# ProPrj_pbsy3_0_2025-02-05.net
KiCad netlist of a schematic drawn in EasyEDA Pro
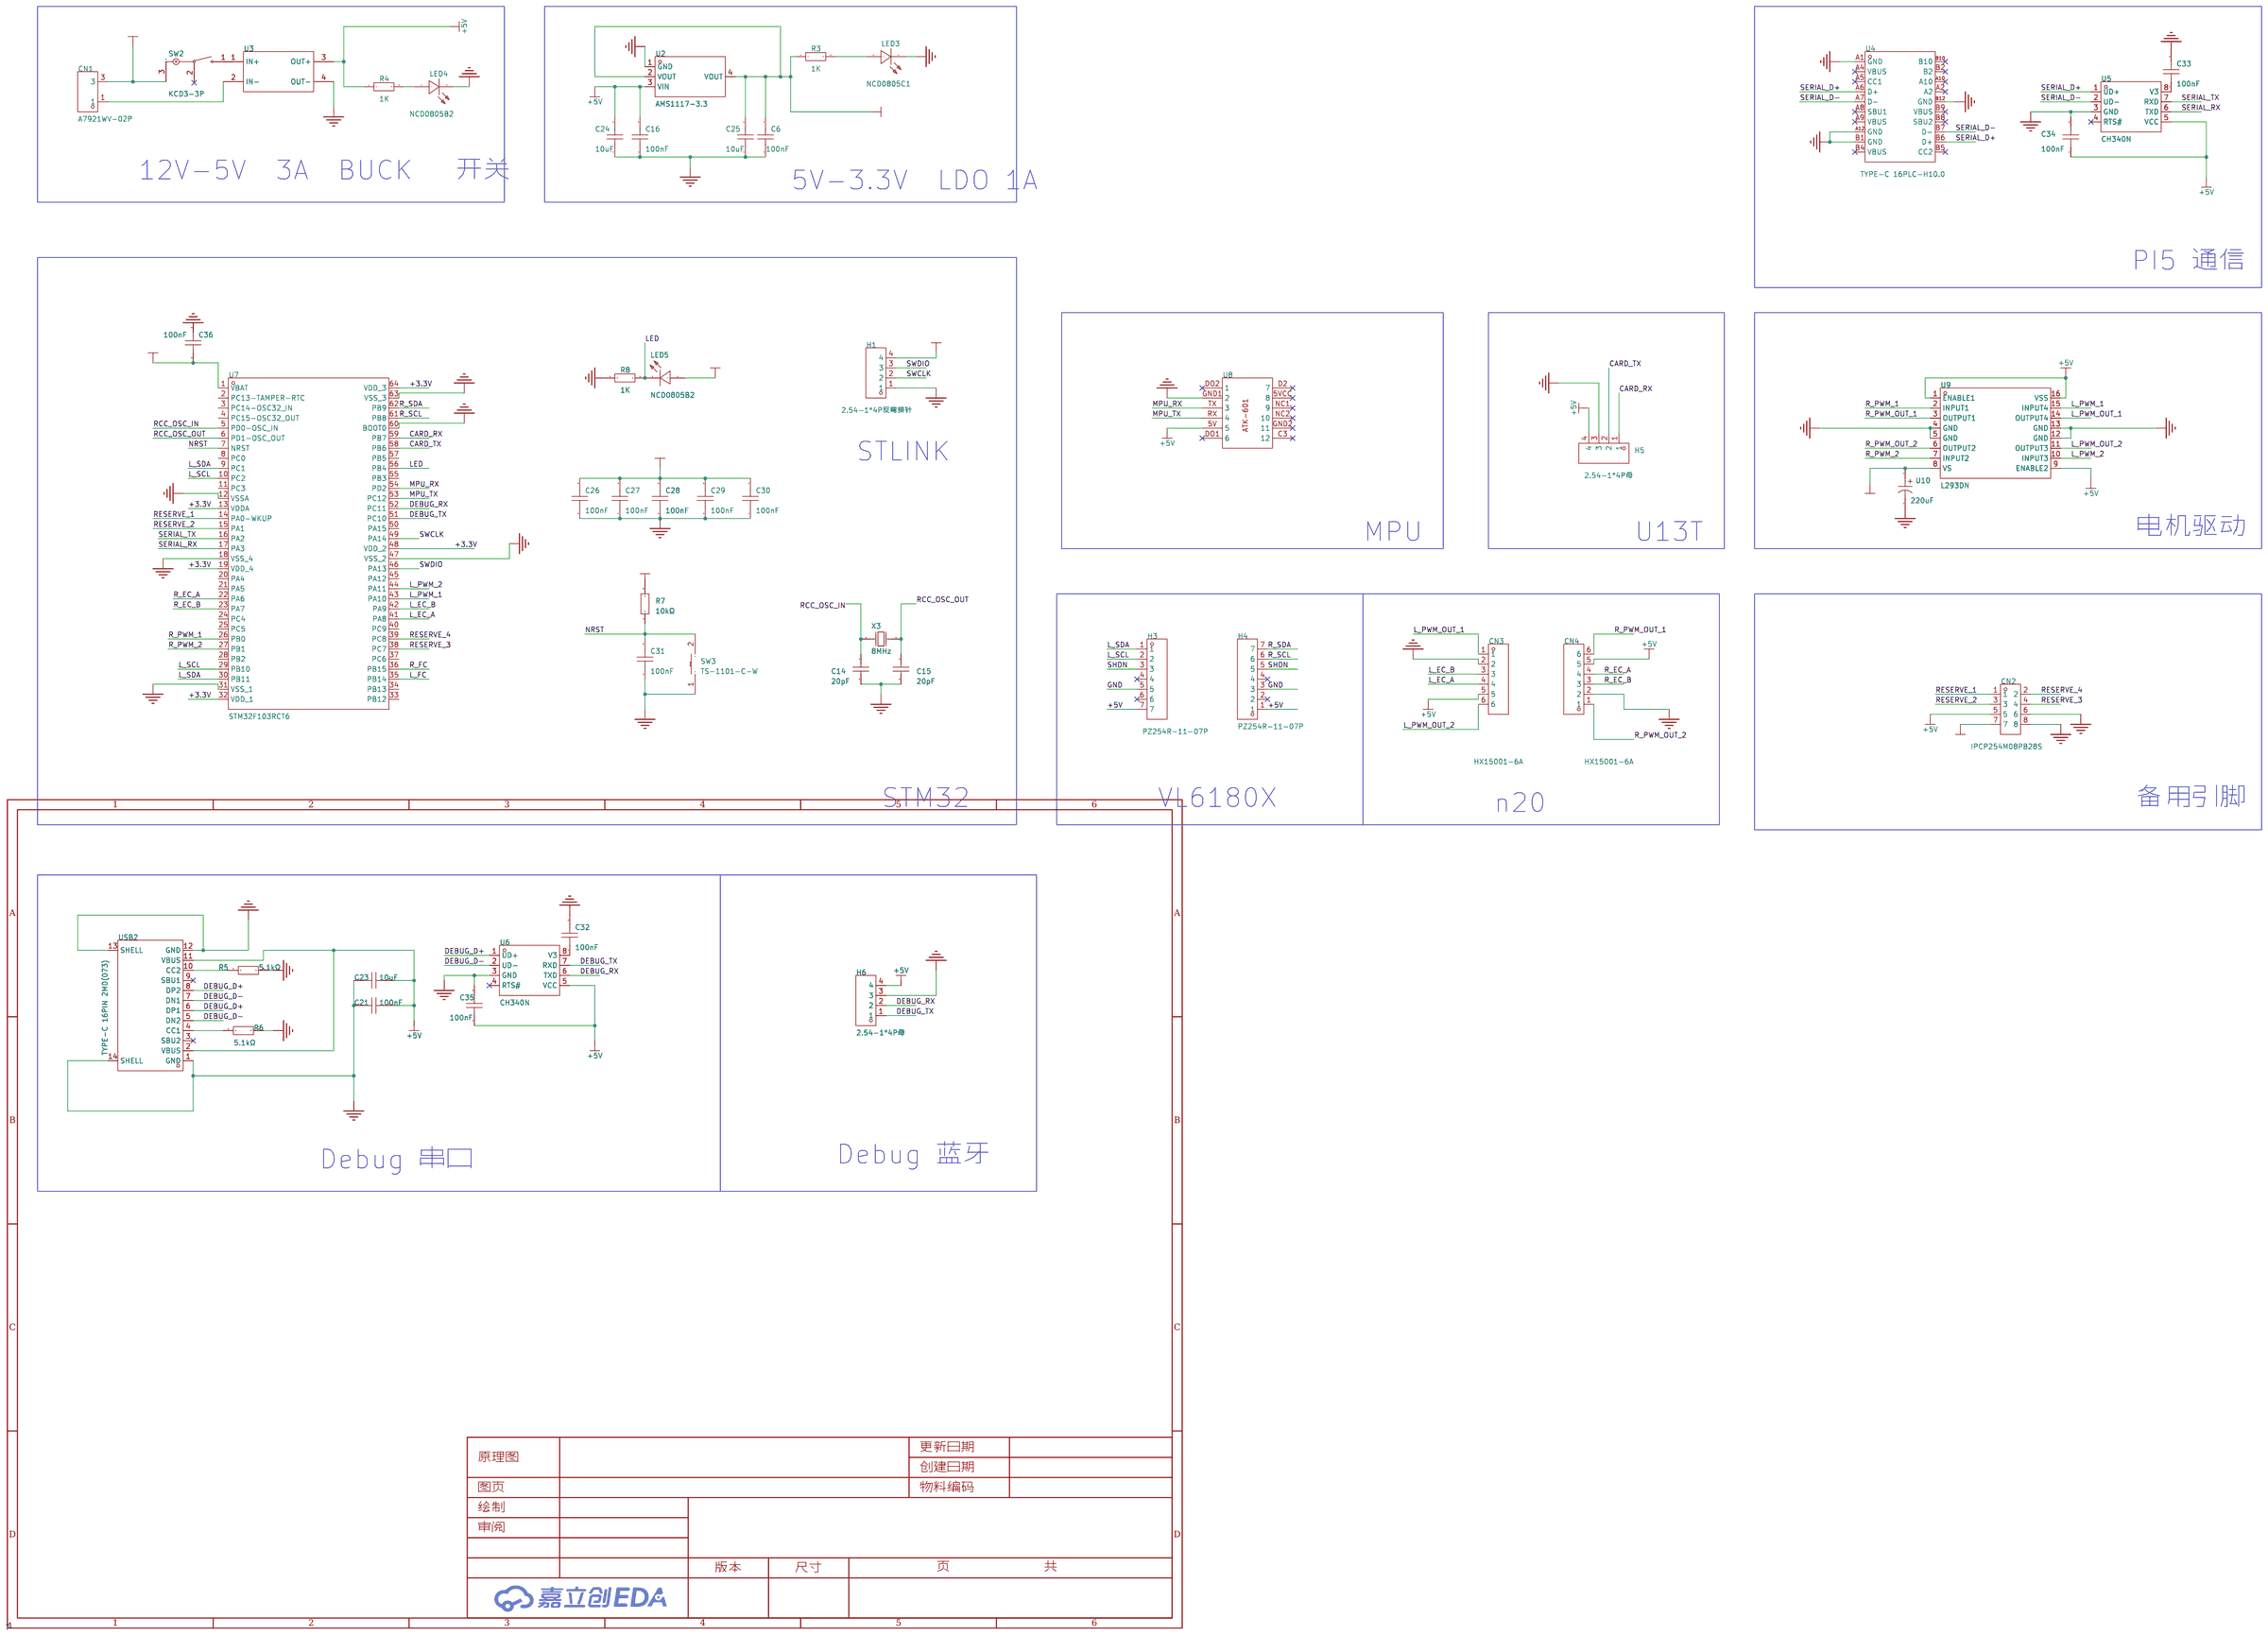
[diagram p0: schematic sheet]

(export (version "E")
  (design (tool "Eeschema 10.0.6"))
  (components
    (comp (ref "C6")
      (value "100nF")
      (footprint "easyedapro:C0603")
      (description "容值:100nF;精度:±10%;额定电压:50V;材质(温度系数):X7R;")
      (fields
        (field (name "Manufacturer Part") "CC0603KRX7R9BB104")
        (field (name "Manufacturer") "YAGEO(国巨)")
      )
      (libsource (lib "easyedapro") (part "CC0603KRX7R9BB104"))
    )
    (comp (ref "C14")
      (value "20pF")
      (footprint "easyedapro:C0805")
      (description "容值:20pF;精度:±5%;额定电压:50V;材质(温度系数):C0G;")
      (fields
        (field (name "Manufacturer Part") "CL21C200JBANNNC")
        (field (name "Manufacturer") "SAMSUNG(三星)")
      )
      (libsource (lib "easyedapro") (part "CL21C200JBANNNC"))
    )
    (comp (ref "C15")
      (value "20pF")
      (footprint "easyedapro:C0805")
      (description "容值:20pF;精度:±5%;额定电压:50V;材质(温度系数):C0G;")
      (fields
        (field (name "Manufacturer Part") "CL21C200JBANNNC")
        (field (name "Manufacturer") "SAMSUNG(三星)")
      )
      (libsource (lib "easyedapro") (part "CL21C200JBANNNC"))
    )
    (comp (ref "C16")
      (value "100nF")
      (footprint "easyedapro:C0603")
      (description "容值:100nF;精度:±10%;额定电压:50V;材质(温度系数):X7R;")
      (fields
        (field (name "Manufacturer Part") "CC0603KRX7R9BB104")
        (field (name "Manufacturer") "YAGEO(国巨)")
      )
      (libsource (lib "easyedapro") (part "CC0603KRX7R9BB104"))
    )
    (comp (ref "C21")
      (value "100nF")
      (footprint "easyedapro:C0603")
      (description "容值:100nF;精度:±10%;额定电压:50V;材质(温度系数):X7R;")
      (fields
        (field (name "Manufacturer Part") "CC0603KRX7R9BB104")
        (field (name "Manufacturer") "YAGEO(国巨)")
      )
      (libsource (lib "easyedapro") (part "CC0603KRX7R9BB104"))
    )
    (comp (ref "C23")
      (value "10uF")
      (footprint "easyedapro:C0805")
      (description "容值:10uF;精度:±10%;额定电压:25V;材质(温度系数):X5R;")
      (fields
        (field (name "Manufacturer Part") "CL21A106KAYNNNE")
        (field (name "Manufacturer") "SAMSUNG(三星)")
      )
      (libsource (lib "easyedapro") (part "CL21A106KAYNNNE"))
    )
    (comp (ref "C24")
      (value "10uF")
      (footprint "easyedapro:C0805")
      (description "容值:10uF;精度:±10%;额定电压:25V;材质(温度系数):X5R;")
      (fields
        (field (name "Manufacturer Part") "CL21A106KAYNNNE")
        (field (name "Manufacturer") "SAMSUNG(三星)")
      )
      (libsource (lib "easyedapro") (part "CL21A106KAYNNNE"))
    )
    (comp (ref "C25")
      (value "10uF")
      (footprint "easyedapro:C0805")
      (description "容值:10uF;精度:±10%;额定电压:25V;材质(温度系数):X5R;")
      (fields
        (field (name "Manufacturer Part") "CL21A106KAYNNNE")
        (field (name "Manufacturer") "SAMSUNG(三星)")
      )
      (libsource (lib "easyedapro") (part "CL21A106KAYNNNE"))
    )
    (comp (ref "C26")
      (value "100nF")
      (footprint "easyedapro:C0603")
      (description "容值:100nF;精度:±10%;额定电压:50V;材质(温度系数):X7R;")
      (fields
        (field (name "Manufacturer Part") "CC0603KRX7R9BB104")
        (field (name "Manufacturer") "YAGEO(国巨)")
      )
      (libsource (lib "easyedapro") (part "CC0603KRX7R9BB104"))
    )
    (comp (ref "C27")
      (value "100nF")
      (footprint "easyedapro:C0603")
      (description "容值:100nF;精度:±10%;额定电压:50V;材质(温度系数):X7R;")
      (fields
        (field (name "Manufacturer Part") "CC0603KRX7R9BB104")
        (field (name "Manufacturer") "YAGEO(国巨)")
      )
      (libsource (lib "easyedapro") (part "CC0603KRX7R9BB104"))
    )
    (comp (ref "C28")
      (value "100nF")
      (footprint "easyedapro:C0603")
      (description "容值:100nF;精度:±10%;额定电压:50V;材质(温度系数):X7R;")
      (fields
        (field (name "Manufacturer Part") "CC0603KRX7R9BB104")
        (field (name "Manufacturer") "YAGEO(国巨)")
      )
      (libsource (lib "easyedapro") (part "CC0603KRX7R9BB104"))
    )
    (comp (ref "C29")
      (value "100nF")
      (footprint "easyedapro:C0603")
      (description "容值:100nF;精度:±10%;额定电压:50V;材质(温度系数):X7R;")
      (fields
        (field (name "Manufacturer Part") "CC0603KRX7R9BB104")
        (field (name "Manufacturer") "YAGEO(国巨)")
      )
      (libsource (lib "easyedapro") (part "CC0603KRX7R9BB104"))
    )
    (comp (ref "C30")
      (value "100nF")
      (footprint "easyedapro:C0603")
      (description "容值:100nF;精度:±10%;额定电压:50V;材质(温度系数):X7R;")
      (fields
        (field (name "Manufacturer Part") "CC0603KRX7R9BB104")
        (field (name "Manufacturer") "YAGEO(国巨)")
      )
      (libsource (lib "easyedapro") (part "CC0603KRX7R9BB104"))
    )
    (comp (ref "C31")
      (value "100nF")
      (footprint "easyedapro:C0603")
      (description "容值:100nF;精度:±10%;额定电压:50V;材质(温度系数):X7R;")
      (fields
        (field (name "Manufacturer Part") "CC0603KRX7R9BB104")
        (field (name "Manufacturer") "YAGEO(国巨)")
      )
      (libsource (lib "easyedapro") (part "CC0603KRX7R9BB104"))
    )
    (comp (ref "C32")
      (value "100nF")
      (footprint "easyedapro:C0603")
      (description "容值:100nF;精度:±10%;额定电压:50V;材质(温度系数):X7R;")
      (fields
        (field (name "Manufacturer Part") "CC0603KRX7R9BB104")
        (field (name "Manufacturer") "YAGEO(国巨)")
      )
      (libsource (lib "easyedapro") (part "CC0603KRX7R9BB104"))
    )
    (comp (ref "C33")
      (value "100nF")
      (footprint "easyedapro:C0603")
      (description "容值:100nF;精度:±10%;额定电压:50V;材质(温度系数):X7R;")
      (fields
        (field (name "Manufacturer Part") "CC0603KRX7R9BB104")
        (field (name "Manufacturer") "YAGEO(国巨)")
      )
      (libsource (lib "easyedapro") (part "CC0603KRX7R9BB104"))
    )
    (comp (ref "C34")
      (value "100nF")
      (footprint "easyedapro:C0603")
      (description "容值:100nF;精度:±10%;额定电压:50V;材质(温度系数):X7R;")
      (fields
        (field (name "Manufacturer Part") "CC0603KRX7R9BB104")
        (field (name "Manufacturer") "YAGEO(国巨)")
      )
      (libsource (lib "easyedapro") (part "CC0603KRX7R9BB104"))
    )
    (comp (ref "C35")
      (value "100nF")
      (footprint "easyedapro:C0603")
      (description "容值:100nF;精度:±10%;额定电压:50V;材质(温度系数):X7R;")
      (fields
        (field (name "Manufacturer Part") "CC0603KRX7R9BB104")
        (field (name "Manufacturer") "YAGEO(国巨)")
      )
      (libsource (lib "easyedapro") (part "CC0603KRX7R9BB104"))
    )
    (comp (ref "C36")
      (value "100nF")
      (footprint "easyedapro:C0603")
      (description "容值:100nF;精度:±10%;额定电压:50V;材质(温度系数):X7R;")
      (fields
        (field (name "Manufacturer Part") "CC0603KRX7R9BB104")
        (field (name "Manufacturer") "YAGEO(国巨)")
      )
      (libsource (lib "easyedapro") (part "CC0603KRX7R9BB104"))
    )
    (comp (ref "CN1")
      (value "A7921WV-02P")
      (footprint "easyedapro:CONN-TH_A7921WR-02P")
      (description "插针结构:1x2P;间距:7.92mm;安装方式:直插;参考系列:-;总PIN数:2P;排数:1;每排PIN数:2;行距:-;额定电流:7A;工作温度范围:-25°C~+85°C;")
      (fields (field (name "Manufacturer") "HR(灿达)"))
      (libsource (lib "easyedapro") (part "A7921WV-02P"))
    )
    (comp (ref "CN2")
      (value "IPCP254M08PB28S")
      (footprint "easyedapro:HDR-SMD_8P-P2.54-V-M-R2-C4-S2.54-LS7.4")
      (fields (field (name "Manufacturer") "INCP"))
      (libsource (lib "easyedapro") (part "IPCP254M08PB28S"))
    )
    (comp (ref "CN3")
      (value "HX15001-6A")
      (footprint "easyedapro:CONN-TH_HX15001-6A")
      (description "插针结构:1x6P;间距:1.5mm;安装方式:直插;参考系列:-;总PIN数:6P;排数:1;每排PIN数:6;行距:-;额定电流:1A;工作温度范围:-25°C~+85°C;")
      (fields (field (name "Manufacturer") "HX(红星)"))
      (libsource (lib "easyedapro") (part "HX15001-6A"))
    )
    (comp (ref "CN4")
      (value "HX15001-6A")
      (footprint "easyedapro:CONN-TH_HX15001-6A")
      (description "插针结构:1x6P;间距:1.5mm;安装方式:直插;参考系列:-;总PIN数:6P;排数:1;每排PIN数:6;行距:-;额定电流:1A;工作温度范围:-25°C~+85°C;")
      (fields (field (name "Manufacturer") "HX(红星)"))
      (libsource (lib "easyedapro") (part "HX15001-6A"))
    )
    (comp (ref "H1")
      (value "2.54-1*4P反弯排针")
      (footprint "easyedapro:HDR-TH_4P-P2.54-H-M-W10.4")
      (fields (field (name "Manufacturer") "BOOMELE(博穆精密)"))
      (libsource (lib "easyedapro") (part "2.54-1*4P反弯排针"))
    )
    (comp (ref "H3")
      (value "PZ254R-11-07P")
      (footprint "easyedapro:HDR-TH_7P-P2.54-H-M-W10.4")
      (fields (field (name "Manufacturer") "XFCN(兴飞)"))
      (libsource (lib "easyedapro") (part "PZ254R-11-07P"))
    )
    (comp (ref "H4")
      (value "PZ254R-11-07P")
      (footprint "easyedapro:HDR-TH_7P-P2.54-H-M-W10.4")
      (fields (field (name "Manufacturer") "XFCN(兴飞)"))
      (libsource (lib "easyedapro") (part "PZ254R-11-07P"))
    )
    (comp (ref "H5")
      (value "2.54-1*4P母")
      (footprint "easyedapro:HDR-TH_4P-P2.54-V-F")
      (fields (field (name "Manufacturer") "BOOMELE(博穆精密)"))
      (libsource (lib "easyedapro") (part "2.54-1*4P母"))
    )
    (comp (ref "H6")
      (value "2.54-1*4P母")
      (footprint "easyedapro:HDR-TH_4P-P2.54-V-F")
      (fields (field (name "Manufacturer") "BOOMELE(博穆精密)"))
      (libsource (lib "easyedapro") (part "2.54-1*4P母"))
    )
    (comp (ref "LED3")
      (value "NCD0805C1")
      (footprint "easyedapro:LED0805-RD")
      (fields (field (name "Manufacturer") "国星光电"))
      (libsource (lib "easyedapro") (part "FC-2012GHK-570A08"))
    )
    (comp (ref "LED4")
      (value "NCD0805B2")
      (footprint "easyedapro:LED0805-R-RD")
      (fields (field (name "Manufacturer") "国星光电"))
      (libsource (lib "easyedapro") (part "FC-A2012BK-470H2"))
    )
    (comp (ref "LED5")
      (value "NCD0805B2")
      (footprint "easyedapro:LED0805-R-RD")
      (fields (field (name "Manufacturer") "国星光电"))
      (libsource (lib "easyedapro") (part "FC-A2012BK-470H2"))
    )
    (comp (ref "R3") (value "1K") (footprint "easyedapro:R0603") (libsource (lib "easyedapro") (part "电阻")))
    (comp (ref "R4") (value "1K") (footprint "easyedapro:R0603") (libsource (lib "easyedapro") (part "电阻")))
    (comp (ref "R5")
      (value "5.1kΩ")
      (footprint "easyedapro:R0603")
      (description "电阻类型:厚膜电阻;阻值:5.1kΩ;精度:±1%;功率:100mW;最大工作电压:75V;温度系数:±100ppm/°C;")
      (fields
        (field (name "Manufacturer Part") "0603WAF5101T5E")
        (field (name "Manufacturer") "UNI-ROYAL(厚声)")
      )
      (libsource (lib "easyedapro") (part "0603WAF5101T5E"))
    )
    (comp (ref "R6")
      (value "5.1kΩ")
      (footprint "easyedapro:R0603")
      (description "电阻类型:厚膜电阻;阻值:5.1kΩ;精度:±1%;功率:100mW;最大工作电压:75V;温度系数:±100ppm/°C;")
      (fields
        (field (name "Manufacturer Part") "0603WAF5101T5E")
        (field (name "Manufacturer") "UNI-ROYAL(厚声)")
      )
      (libsource (lib "easyedapro") (part "0603WAF5101T5E"))
    )
    (comp (ref "R7")
      (value "10kΩ")
      (footprint "easyedapro:R0603")
      (description "电阻类型:厚膜电阻;阻值:10kΩ;精度:±1%;功率:100mW;最大工作电压:75V;温度系数:±100ppm/°C;")
      (fields
        (field (name "Manufacturer Part") "0603WAF1002T5E")
        (field (name "Manufacturer") "UNI-ROYAL(厚声)")
      )
      (libsource (lib "easyedapro") (part "0603WAF1002T5E"))
    )
    (comp (ref "R8") (value "1K") (footprint "easyedapro:R0603") (libsource (lib "easyedapro") (part "电阻")))
    (comp (ref "SW2")
      (value "KCD3-3P")
      (footprint "easyedapro:SW-TH_KCD3-3P")
      (description "带灯:红灯;引脚样式:焊片;额定电流:15A;额定电压(AC):250V;额定电压(DC):-;电路结构:单刀单掷;机械寿命:1万次;")
      (fields (field (name "Manufacturer") "SHOU HAN(首韩)"))
      (libsource (lib "easyedapro") (part "KCD3-3P"))
    )
    (comp (ref "SW3")
      (value "TS-1101-C-W")
      (footprint "easyedapro:SW-SMD_L6.0-W3.3-LS8.0")
      (fields (field (name "Manufacturer") "XKB Connectivity(中国星坤)"))
      (libsource (lib "easyedapro") (part "TS-1101-C-W"))
    )
    (comp (ref "U2")
      (value "AMS1117-3.3")
      (footprint "easyedapro:SOT-223-3_L6.5-W3.4-P2.30-LS7.0-BR")
      (description "输出类型:固定;最大输入电压:-;输出电压:3.3V;最大输出电流:1A;电源纹波抑制比(PSRR):72dB@(120Hz);输出极性:正极;")
      (fields (field (name "Manufacturer") "AMS"))
      (libsource (lib "easyedapro") (part "AMS1117-3.3"))
    )
    (comp (ref "U3")
      (value "~")
      (footprint "easyedapro:12v-5v")
      (libsource (lib "easyedapro") (part "12v-5v"))
    )
    (comp (ref "U4")
      (value "TYPE-C 16PLC-H10.0")
      (footprint "easyedapro:TYPE-C-TH_16PLC-H10.0")
      (fields (field (name "Manufacturer") "SHOU HAN(首韩)"))
      (libsource (lib "easyedapro") (part "TYPE-C 16PLC-H10.0"))
    )
    (comp (ref "U5")
      (value "CH340N")
      (footprint "easyedapro:SOP-8_L4.9-W3.9-P1.27-LS6.0-BL")
      (description "应用功能:USB转串口;接口协议:USB 2.0;通道数:1;数据速率:2Mbps;")
      (fields (field (name "Manufacturer") "WCH(南京沁恒)"))
      (libsource (lib "easyedapro") (part "CH340N_C2977777"))
    )
    (comp (ref "U6")
      (value "CH340N")
      (footprint "easyedapro:SOP-8_L4.9-W3.9-P1.27-LS6.0-BL")
      (description "应用功能:USB转串口;接口协议:USB 2.0;通道数:1;数据速率:2Mbps;")
      (fields (field (name "Manufacturer") "WCH(南京沁恒)"))
      (libsource (lib "easyedapro") (part "CH340N_C2977777"))
    )
    (comp (ref "U7")
      (value "STM32F103RCT6")
      (footprint "easyedapro:LQFP-64_L10.0-W10.0-P0.50-LS12.0-BL")
      (description "CPU内核:ARM-M3;CPU最大主频:72MHz;应用领域:-;")
      (fields (field (name "Manufacturer") "ST(意法半导体)"))
      (libsource (lib "easyedapro") (part "STM32F103RCT6"))
    )
    (comp (ref "U8")
      (value "~")
      (footprint "easyedapro:ATK-601")
      (libsource (lib "easyedapro") (part "ATK-601"))
    )
    (comp (ref "U9")
      (value "L293DN")
      (footprint "easyedapro:DIP-16_L19.2-W6.6-P2.54-LS7.6-BL")
      (fields (field (name "Manufacturer") "HGSEMI(华冠)"))
      (libsource (lib "easyedapro") (part "L293DN"))
    )
    (comp (ref "U10")
      (value "220uF")
      (footprint "easyedapro:CAP-SMD_BD10.0-L10.3-W10.3-LS11.3-FD")
      (description "容值:220uF;精度:±20%;额定电压:50V;纹波电流:230mA@120Hz;等效串联电阻:-;")
      (fields
        (field (name "Manufacturer Part") "RVT1H221M1010 220UF 50V")
        (field (name "Manufacturer") "DMBJ(振宝佳)")
      )
      (libsource (lib "easyedapro") (part "RVT1H221M1010 220UF 50V"))
    )
    (comp (ref "USB2")
      (value "TYPE-C 16PIN 2MD(073)")
      (footprint "easyedapro:USB-C-SMD_TYPE-C-6PIN-2MD-073")
      (description "连接器类型:Type-C;标准:USB 3.1;公母:母;安装方式:卧贴;触点数量:16P;端口数量:1;额定电流 - 电源:5A;工作温度范围:-25°C~+85°C;")
      (fields (field (name "Manufacturer") "SHOU HAN(首韩)"))
      (libsource (lib "easyedapro") (part "TYPE-C 16PIN 2MD(073)"))
    )
    (comp (ref "X3")
      (value "8MHz")
      (footprint "easyedapro:CRYSTAL-SMD_L5.0-W3.2")
      (description "晶振类型:贴片晶振;频率:8MHz;常温频差:±10ppm;外接负载电容:20pF;频率稳定度(全温):±20ppm;")
      (fields (field (name "Manufacturer Part") "X50328MSB2GI") (field (name "Manufacturer") "YXC(扬兴晶振)"))
      (libsource (lib "easyedapro") (part "X50328MSB2GI"))
    )
  )
  (nets
    (net (code "1") (name "+3.3V") (class "Default")
      (node (ref "C25") (pin "2") (pinfunction "2_2") (pintype "unspecified"))
      (node (ref "C26") (pin "2") (pinfunction "2_2") (pintype "unspecified"))
      (node (ref "C27") (pin "2") (pinfunction "2_2") (pintype "unspecified"))
      (node (ref "C28") (pin "2") (pinfunction "2_2") (pintype "unspecified"))
      (node (ref "C29") (pin "2") (pinfunction "2_2") (pintype "unspecified"))
      (node (ref "C30") (pin "2") (pinfunction "2_2") (pintype "unspecified"))
      (node (ref "C36") (pin "1") (pinfunction "1_1") (pintype "unspecified"))
      (node (ref "C6") (pin "2") (pinfunction "2_2") (pintype "unspecified"))
      (node (ref "CN2") (pin "7") (pinfunction "7_7") (pintype "unspecified"))
      (node (ref "H1") (pin "4") (pinfunction "4_4") (pintype "unspecified"))
      (node (ref "LED5") (pin "1") (pinfunction "+_1") (pintype "unspecified"))
      (node (ref "R3") (pin "1") (pinfunction "1_1") (pintype "input"))
      (node (ref "R7") (pin "2") (pinfunction "2_2") (pintype "input"))
      (node (ref "U2") (pin "2") (pinfunction "VOUT_2") (pintype "unspecified"))
      (node (ref "U2") (pin "4") (pinfunction "VOUT_4") (pintype "unspecified"))
      (node (ref "U7") (pin "1") (pinfunction "VBAT_1") (pintype "unspecified"))
      (node (ref "U7") (pin "13") (pinfunction "VDDA_13") (pintype "unspecified"))
      (node (ref "U7") (pin "19") (pinfunction "VDD_4_19") (pintype "unspecified"))
      (node (ref "U7") (pin "32") (pinfunction "VDD_1_32") (pintype "unspecified"))
      (node (ref "U7") (pin "48") (pinfunction "VDD_2_48") (pintype "unspecified"))
      (node (ref "U7") (pin "64") (pinfunction "VDD_3_64") (pintype "unspecified"))
    )
    (net (code "2") (name "+5V") (class "Default")
      (node (ref "C16") (pin "2") (pinfunction "2_2") (pintype "unspecified"))
      (node (ref "C21") (pin "2") (pinfunction "2_2") (pintype "unspecified"))
      (node (ref "C23") (pin "2") (pinfunction "2_2") (pintype "unspecified"))
      (node (ref "C24") (pin "2") (pinfunction "2_2") (pintype "unspecified"))
      (node (ref "C34") (pin "1") (pinfunction "1_1") (pintype "unspecified"))
      (node (ref "C35") (pin "1") (pinfunction "1_1") (pintype "unspecified"))
      (node (ref "CN2") (pin "5") (pinfunction "5_5") (pintype "unspecified"))
      (node (ref "CN3") (pin "5") (pinfunction "5_5") (pintype "unspecified"))
      (node (ref "CN4") (pin "5") (pinfunction "5_5") (pintype "unspecified"))
      (node (ref "H3") (pin "7") (pinfunction "7_7") (pintype "unspecified"))
      (node (ref "H4") (pin "1") (pinfunction "1_1") (pintype "unspecified"))
      (node (ref "H5") (pin "4") (pinfunction "4_4") (pintype "unspecified"))
      (node (ref "H6") (pin "4") (pinfunction "4_4") (pintype "unspecified"))
      (node (ref "R4") (pin "1") (pinfunction "1_1") (pintype "input"))
      (node (ref "U2") (pin "3") (pinfunction "VIN_3") (pintype "unspecified"))
      (node (ref "U3") (pin "3") (pinfunction "OUT+_3") (pintype "input"))
      (node (ref "U5") (pin "5") (pinfunction "VCC_5") (pintype "unspecified"))
      (node (ref "U6") (pin "5") (pinfunction "VCC_5") (pintype "unspecified"))
      (node (ref "U8") (pin "5V") (pinfunction "5_5V") (pintype "input"))
      (node (ref "U9") (pin "1") (pinfunction "ENABLE1_1") (pintype "unspecified"))
      (node (ref "U9") (pin "16") (pinfunction "VSS_16") (pintype "unspecified"))
      (node (ref "U9") (pin "9") (pinfunction "ENABLE2_9") (pintype "unspecified"))
      (node (ref "USB2") (pin "11") (pinfunction "VBUS_11") (pintype "unspecified"))
      (node (ref "USB2") (pin "2") (pinfunction "VBUS_2") (pintype "unspecified"))
    )
    (net (code "3") (name "+12V") (class "Default")
      (node (ref "CN1") (pin "3") (pinfunction "3_3") (pintype "unspecified"))
      (node (ref "SW2") (pin "3") (pinfunction "3_3") (pintype "unspecified"))
      (node (ref "U10") (pin "1") (pinfunction "1_1") (pintype "input"))
      (node (ref "U9") (pin "8") (pinfunction "VS_8") (pintype "unspecified"))
    )
    (net (code "4") (name "/CARD_RX") (class "Default")
      (node (ref "H5") (pin "1") (pinfunction "1_1") (pintype "unspecified"))
      (node (ref "U7") (pin "59") (pinfunction "PB7_59") (pintype "unspecified"))
    )
    (net (code "5") (name "/CARD_TX") (class "Default")
      (node (ref "H5") (pin "2") (pinfunction "2_2") (pintype "unspecified"))
      (node (ref "U7") (pin "58") (pinfunction "PB6_58") (pintype "unspecified"))
    )
    (net (code "6") (name "/DEBUG_D+") (class "Default")
      (node (ref "U6") (pin "1") (pinfunction "UD+_1") (pintype "unspecified"))
      (node (ref "USB2") (pin "6") (pinfunction "DP1_6") (pintype "unspecified"))
      (node (ref "USB2") (pin "8") (pinfunction "DP2_8") (pintype "unspecified"))
    )
    (net (code "7") (name "/DEBUG_D-") (class "Default")
      (node (ref "U6") (pin "2") (pinfunction "UD-_2") (pintype "unspecified"))
      (node (ref "USB2") (pin "5") (pinfunction "DN2_5") (pintype "unspecified"))
      (node (ref "USB2") (pin "7") (pinfunction "DN1_7") (pintype "unspecified"))
    )
    (net (code "8") (name "/DEBUG_RX") (class "Default")
      (node (ref "H6") (pin "2") (pinfunction "2_2") (pintype "unspecified"))
      (node (ref "U6") (pin "6") (pinfunction "TXD_6") (pintype "unspecified"))
      (node (ref "U7") (pin "52") (pinfunction "PC11_52") (pintype "unspecified"))
    )
    (net (code "9") (name "/DEBUG_TX") (class "Default")
      (node (ref "H6") (pin "1") (pinfunction "1_1") (pintype "unspecified"))
      (node (ref "U6") (pin "7") (pinfunction "RXD_7") (pintype "unspecified"))
      (node (ref "U7") (pin "51") (pinfunction "PC10_51") (pintype "unspecified"))
    )
    (net (code "10") (name "/LED") (class "Default")
      (node (ref "LED5") (pin "2") (pinfunction "-_2") (pintype "unspecified"))
      (node (ref "R8") (pin "2") (pinfunction "2_2") (pintype "input"))
      (node (ref "U7") (pin "56") (pinfunction "PB4_56") (pintype "unspecified"))
    )
    (net (code "11") (name "/L_EC_A") (class "Default")
      (node (ref "CN3") (pin "4") (pinfunction "4_4") (pintype "unspecified"))
      (node (ref "U7") (pin "41") (pinfunction "PA8_41") (pintype "unspecified"))
    )
    (net (code "12") (name "/L_EC_B") (class "Default")
      (node (ref "CN3") (pin "3") (pinfunction "3_3") (pintype "unspecified"))
      (node (ref "U7") (pin "42") (pinfunction "PA9_42") (pintype "unspecified"))
    )
    (net (code "13") (name "/L_FC") (class "Default")
      (node (ref "U7") (pin "35") (pinfunction "PB14_35") (pintype "unspecified"))
    )
    (net (code "14") (name "/L_PWM_1") (class "Default")
      (node (ref "U7") (pin "43") (pinfunction "PA10_43") (pintype "unspecified"))
      (node (ref "U9") (pin "15") (pinfunction "INPUT4_15") (pintype "unspecified"))
    )
    (net (code "15") (name "/L_PWM_2") (class "Default")
      (node (ref "U7") (pin "44") (pinfunction "PA11_44") (pintype "unspecified"))
      (node (ref "U9") (pin "10") (pinfunction "INPUT3_10") (pintype "unspecified"))
    )
    (net (code "16") (name "/L_PWM_OUT_1") (class "Default")
      (node (ref "CN3") (pin "1") (pinfunction "1_1") (pintype "unspecified"))
      (node (ref "U9") (pin "14") (pinfunction "OUTPUT4_14") (pintype "unspecified"))
    )
    (net (code "17") (name "/L_PWM_OUT_2") (class "Default")
      (node (ref "CN3") (pin "6") (pinfunction "6_6") (pintype "unspecified"))
      (node (ref "U9") (pin "11") (pinfunction "OUTPUT3_11") (pintype "unspecified"))
    )
    (net (code "18") (name "/L_SCL") (class "Default")
      (node (ref "H3") (pin "2") (pinfunction "2_2") (pintype "unspecified"))
      (node (ref "U7") (pin "10") (pinfunction "PC2_10") (pintype "unspecified"))
      (node (ref "U7") (pin "29") (pinfunction "PB10_29") (pintype "unspecified"))
    )
    (net (code "19") (name "/L_SDA") (class "Default")
      (node (ref "H3") (pin "1") (pinfunction "1_1") (pintype "unspecified"))
      (node (ref "U7") (pin "30") (pinfunction "PB11_30") (pintype "unspecified"))
      (node (ref "U7") (pin "9") (pinfunction "PC1_9") (pintype "unspecified"))
    )
    (net (code "20") (name "/MPU_RX") (class "Default")
      (node (ref "U7") (pin "54") (pinfunction "PD2_54") (pintype "unspecified"))
      (node (ref "U8") (pin "TX") (pinfunction "3_TX") (pintype "input"))
    )
    (net (code "21") (name "/MPU_TX") (class "Default")
      (node (ref "U7") (pin "53") (pinfunction "PC12_53") (pintype "unspecified"))
      (node (ref "U8") (pin "RX") (pinfunction "4_RX") (pintype "input"))
    )
    (net (code "22") (name "/NRST") (class "Default")
      (node (ref "C31") (pin "2") (pinfunction "2_2") (pintype "unspecified"))
      (node (ref "R7") (pin "1") (pinfunction "1_1") (pintype "input"))
      (node (ref "SW3") (pin "2") (pinfunction "2_2") (pintype "unspecified"))
      (node (ref "U7") (pin "7") (pinfunction "NRST_7") (pintype "unspecified"))
    )
    (net (code "23") (name "/RCC_OSC_IN") (class "Default")
      (node (ref "C14") (pin "2") (pinfunction "2_2") (pintype "input"))
      (node (ref "U7") (pin "5") (pinfunction "PD0-OSC_IN_5") (pintype "unspecified"))
      (node (ref "X3") (pin "1") (pinfunction "OSC1_1") (pintype "input"))
    )
    (net (code "24") (name "/RCC_OSC_OUT") (class "Default")
      (node (ref "C15") (pin "2") (pinfunction "2_2") (pintype "input"))
      (node (ref "U7") (pin "6") (pinfunction "PD1-OSC_OUT_6") (pintype "unspecified"))
      (node (ref "X3") (pin "2") (pinfunction "OSC2_2") (pintype "input"))
    )
    (net (code "25") (name "/RESERVE_1") (class "Default")
      (node (ref "CN2") (pin "1") (pinfunction "1_1") (pintype "unspecified"))
      (node (ref "U7") (pin "14") (pinfunction "PA0-WKUP_14") (pintype "unspecified"))
    )
    (net (code "26") (name "/RESERVE_2") (class "Default")
      (node (ref "CN2") (pin "3") (pinfunction "3_3") (pintype "unspecified"))
      (node (ref "U7") (pin "15") (pinfunction "PA1_15") (pintype "unspecified"))
    )
    (net (code "27") (name "/RESERVE_3") (class "Default")
      (node (ref "CN2") (pin "4") (pinfunction "4_4") (pintype "unspecified"))
      (node (ref "U7") (pin "38") (pinfunction "PC7_38") (pintype "unspecified"))
    )
    (net (code "28") (name "/RESERVE_4") (class "Default")
      (node (ref "CN2") (pin "2") (pinfunction "2_2") (pintype "unspecified"))
      (node (ref "U7") (pin "39") (pinfunction "PC8_39") (pintype "unspecified"))
    )
    (net (code "29") (name "/R_EC_A") (class "Default")
      (node (ref "CN4") (pin "4") (pinfunction "4_4") (pintype "unspecified"))
      (node (ref "U7") (pin "22") (pinfunction "PA6_22") (pintype "unspecified"))
    )
    (net (code "30") (name "/R_EC_B") (class "Default")
      (node (ref "CN4") (pin "3") (pinfunction "3_3") (pintype "unspecified"))
      (node (ref "U7") (pin "23") (pinfunction "PA7_23") (pintype "unspecified"))
    )
    (net (code "31") (name "/R_FC") (class "Default")
      (node (ref "U7") (pin "36") (pinfunction "PB15_36") (pintype "unspecified"))
    )
    (net (code "32") (name "/R_PWM_1") (class "Default")
      (node (ref "U7") (pin "26") (pinfunction "PB0_26") (pintype "unspecified"))
      (node (ref "U9") (pin "2") (pinfunction "INPUT1_2") (pintype "unspecified"))
    )
    (net (code "33") (name "/R_PWM_2") (class "Default")
      (node (ref "U7") (pin "27") (pinfunction "PB1_27") (pintype "unspecified"))
      (node (ref "U9") (pin "7") (pinfunction "INPUT2_7") (pintype "unspecified"))
    )
    (net (code "34") (name "/R_PWM_OUT_1") (class "Default")
      (node (ref "CN4") (pin "6") (pinfunction "6_6") (pintype "unspecified"))
      (node (ref "U9") (pin "3") (pinfunction "OUTPUT1_3") (pintype "unspecified"))
    )
    (net (code "35") (name "/R_PWM_OUT_2") (class "Default")
      (node (ref "CN4") (pin "1") (pinfunction "1_1") (pintype "unspecified"))
      (node (ref "U9") (pin "6") (pinfunction "OUTPUT2_6") (pintype "unspecified"))
    )
    (net (code "36") (name "/R_SCL") (class "Default")
      (node (ref "H4") (pin "6") (pinfunction "6_6") (pintype "unspecified"))
      (node (ref "U7") (pin "61") (pinfunction "PB8_61") (pintype "unspecified"))
    )
    (net (code "37") (name "/R_SDA") (class "Default")
      (node (ref "H4") (pin "7") (pinfunction "7_7") (pintype "unspecified"))
      (node (ref "U7") (pin "62") (pinfunction "PB9_62") (pintype "unspecified"))
    )
    (net (code "38") (name "/SERIAL_D+") (class "Default")
      (node (ref "U4") (pin "A6") (pinfunction "D+_A6") (pintype "unspecified"))
      (node (ref "U4") (pin "B6") (pinfunction "D+_B6") (pintype "unspecified"))
      (node (ref "U5") (pin "1") (pinfunction "UD+_1") (pintype "unspecified"))
    )
    (net (code "39") (name "/SERIAL_D-") (class "Default")
      (node (ref "U4") (pin "A7") (pinfunction "D-_A7") (pintype "unspecified"))
      (node (ref "U4") (pin "B7") (pinfunction "D-_B7") (pintype "unspecified"))
      (node (ref "U5") (pin "2") (pinfunction "UD-_2") (pintype "unspecified"))
    )
    (net (code "40") (name "/SERIAL_RX") (class "Default")
      (node (ref "U5") (pin "6") (pinfunction "TXD_6") (pintype "unspecified"))
      (node (ref "U7") (pin "17") (pinfunction "PA3_17") (pintype "unspecified"))
    )
    (net (code "41") (name "/SERIAL_TX") (class "Default")
      (node (ref "U5") (pin "7") (pinfunction "RXD_7") (pintype "unspecified"))
      (node (ref "U7") (pin "16") (pinfunction "PA2_16") (pintype "unspecified"))
    )
    (net (code "42") (name "/SHDN") (class "Default")
      (node (ref "H3") (pin "3") (pinfunction "3_3") (pintype "unspecified"))
      (node (ref "H4") (pin "5") (pinfunction "5_5") (pintype "unspecified"))
    )
    (net (code "43") (name "/SWCLK") (class "Default")
      (node (ref "H1") (pin "2") (pinfunction "2_2") (pintype "unspecified"))
      (node (ref "U7") (pin "49") (pinfunction "PA14_49") (pintype "unspecified"))
    )
    (net (code "44") (name "/SWDIO") (class "Default")
      (node (ref "H1") (pin "3") (pinfunction "3_3") (pintype "unspecified"))
      (node (ref "U7") (pin "46") (pinfunction "PA13_46") (pintype "unspecified"))
    )
    (net (code "45") (name "GND") (class "Default")
      (node (ref "C14") (pin "1") (pinfunction "1_1") (pintype "input"))
      (node (ref "C15") (pin "1") (pinfunction "1_1") (pintype "input"))
      (node (ref "C16") (pin "1") (pinfunction "1_1") (pintype "unspecified"))
      (node (ref "C21") (pin "1") (pinfunction "1_1") (pintype "unspecified"))
      (node (ref "C23") (pin "1") (pinfunction "1_1") (pintype "unspecified"))
      (node (ref "C24") (pin "1") (pinfunction "1_1") (pintype "unspecified"))
      (node (ref "C25") (pin "1") (pinfunction "1_1") (pintype "unspecified"))
      (node (ref "C26") (pin "1") (pinfunction "1_1") (pintype "unspecified"))
      (node (ref "C27") (pin "1") (pinfunction "1_1") (pintype "unspecified"))
      (node (ref "C28") (pin "1") (pinfunction "1_1") (pintype "unspecified"))
      (node (ref "C29") (pin "1") (pinfunction "1_1") (pintype "unspecified"))
      (node (ref "C30") (pin "1") (pinfunction "1_1") (pintype "unspecified"))
      (node (ref "C31") (pin "1") (pinfunction "1_1") (pintype "unspecified"))
      (node (ref "C32") (pin "2") (pinfunction "2_2") (pintype "unspecified"))
      (node (ref "C33") (pin "2") (pinfunction "2_2") (pintype "unspecified"))
      (node (ref "C34") (pin "2") (pinfunction "2_2") (pintype "unspecified"))
      (node (ref "C35") (pin "2") (pinfunction "2_2") (pintype "unspecified"))
      (node (ref "C36") (pin "2") (pinfunction "2_2") (pintype "unspecified"))
      (node (ref "C6") (pin "1") (pinfunction "1_1") (pintype "unspecified"))
      (node (ref "CN2") (pin "6") (pinfunction "6_6") (pintype "unspecified"))
      (node (ref "CN2") (pin "8") (pinfunction "8_8") (pintype "unspecified"))
      (node (ref "CN3") (pin "2") (pinfunction "2_2") (pintype "unspecified"))
      (node (ref "CN4") (pin "2") (pinfunction "2_2") (pintype "unspecified"))
      (node (ref "H1") (pin "1") (pinfunction "1_1") (pintype "unspecified"))
      (node (ref "H3") (pin "5") (pinfunction "5_5") (pintype "unspecified"))
      (node (ref "H4") (pin "3") (pinfunction "3_3") (pintype "unspecified"))
      (node (ref "H5") (pin "3") (pinfunction "3_3") (pintype "unspecified"))
      (node (ref "H6") (pin "3") (pinfunction "3_3") (pintype "unspecified"))
      (node (ref "LED3") (pin "1") (pinfunction "K_1") (pintype "unspecified"))
      (node (ref "LED4") (pin "2") (pinfunction "-_2") (pintype "unspecified"))
      (node (ref "R5") (pin "2") (pinfunction "2_2") (pintype "input"))
      (node (ref "R6") (pin "2") (pinfunction "2_2") (pintype "input"))
      (node (ref "R8") (pin "1") (pinfunction "1_1") (pintype "input"))
      (node (ref "SW3") (pin "1") (pinfunction "1_1") (pintype "unspecified"))
      (node (ref "U10") (pin "2") (pinfunction "2_2") (pintype "input"))
      (node (ref "U2") (pin "1") (pinfunction "GND_1") (pintype "unspecified"))
      (node (ref "U3") (pin "4") (pinfunction "OUT-_4") (pintype "input"))
      (node (ref "U4") (pin "A1") (pinfunction "GND_A1") (pintype "unspecified"))
      (node (ref "U4") (pin "A12") (pinfunction "GND_A12") (pintype "unspecified"))
      (node (ref "U4") (pin "B1") (pinfunction "GND_B1") (pintype "unspecified"))
      (node (ref "U4") (pin "B12") (pinfunction "GND_B12") (pintype "unspecified"))
      (node (ref "U5") (pin "3") (pinfunction "GND_3") (pintype "unspecified"))
      (node (ref "U6") (pin "3") (pinfunction "GND_3") (pintype "unspecified"))
      (node (ref "U7") (pin "12") (pinfunction "VSSA_12") (pintype "unspecified"))
      (node (ref "U7") (pin "18") (pinfunction "VSS_4_18") (pintype "unspecified"))
      (node (ref "U7") (pin "31") (pinfunction "VSS_1_31") (pintype "unspecified"))
      (node (ref "U7") (pin "47") (pinfunction "VSS_2_47") (pintype "unspecified"))
      (node (ref "U7") (pin "60") (pinfunction "BOOT0_60") (pintype "unspecified"))
      (node (ref "U7") (pin "63") (pinfunction "VSS_3_63") (pintype "unspecified"))
      (node (ref "U8") (pin "GND1") (pinfunction "2_GND1") (pintype "input"))
      (node (ref "U9") (pin "12") (pinfunction "GND_12") (pintype "unspecified"))
      (node (ref "U9") (pin "13") (pinfunction "GND_13") (pintype "unspecified"))
      (node (ref "U9") (pin "4") (pinfunction "GND_4") (pintype "unspecified"))
      (node (ref "U9") (pin "5") (pinfunction "GND_5") (pintype "unspecified"))
      (node (ref "USB2") (pin "1") (pinfunction "GND_1") (pintype "unspecified"))
      (node (ref "USB2") (pin "12") (pinfunction "GND_12") (pintype "unspecified"))
      (node (ref "USB2") (pin "13") (pinfunction "SHELL_13") (pintype "unspecified"))
      (node (ref "USB2") (pin "14") (pinfunction "SHELL_14") (pintype "unspecified"))
    )
    (net (code "46") (name "Net-(LED3-A)") (class "Default")
      (node (ref "LED3") (pin "2") (pinfunction "A_2") (pintype "unspecified"))
      (node (ref "R3") (pin "2") (pinfunction "2_2") (pintype "input"))
    )
    (net (code "47") (name "Net-(LED4-+)") (class "Default")
      (node (ref "LED4") (pin "1") (pinfunction "+_1") (pintype "unspecified"))
      (node (ref "R4") (pin "2") (pinfunction "2_2") (pintype "input"))
    )
    (net (code "48") (name "Net-(U3-IN+)") (class "Default")
      (node (ref "SW2") (pin "1") (pinfunction "1_1") (pintype "unspecified"))
      (node (ref "U3") (pin "1") (pinfunction "IN+_1") (pintype "input"))
    )
    (net (code "49") (name "Net-(U3-IN-)") (class "Default")
      (node (ref "CN1") (pin "1") (pinfunction "1_1") (pintype "unspecified"))
      (node (ref "U3") (pin "2") (pinfunction "IN-_2") (pintype "input"))
    )
    (net (code "50") (name "Net-(U5-V3)") (class "Default")
      (node (ref "C33") (pin "1") (pinfunction "1_1") (pintype "unspecified"))
      (node (ref "U5") (pin "8") (pinfunction "V3_8") (pintype "unspecified"))
    )
    (net (code "51") (name "Net-(U6-V3)") (class "Default")
      (node (ref "C32") (pin "1") (pinfunction "1_1") (pintype "unspecified"))
      (node (ref "U6") (pin "8") (pinfunction "V3_8") (pintype "unspecified"))
    )
    (net (code "52") (name "Net-(USB2-CC1)") (class "Default")
      (node (ref "R6") (pin "1") (pinfunction "1_1") (pintype "input"))
      (node (ref "USB2") (pin "4") (pinfunction "CC1_4") (pintype "unspecified"))
    )
    (net (code "53") (name "Net-(USB2-CC2)") (class "Default")
      (node (ref "R5") (pin "1") (pinfunction "1_1") (pintype "input"))
      (node (ref "USB2") (pin "10") (pinfunction "CC2_10") (pintype "unspecified"))
    )
    (net (code "54") (name "unconnected-(H3-Pad4)") (class "Default")
      (node (ref "H3") (pin "4") (pinfunction "4_4") (pintype "unspecified+no_connect"))
    )
    (net (code "55") (name "unconnected-(H3-Pad6)") (class "Default")
      (node (ref "H3") (pin "6") (pinfunction "6_6") (pintype "unspecified+no_connect"))
    )
    (net (code "56") (name "unconnected-(H4-Pad2)") (class "Default")
      (node (ref "H4") (pin "2") (pinfunction "2_2") (pintype "unspecified+no_connect"))
    )
    (net (code "57") (name "unconnected-(H4-Pad4)") (class "Default")
      (node (ref "H4") (pin "4") (pinfunction "4_4") (pintype "unspecified+no_connect"))
    )
    (net (code "58") (name "unconnected-(SW2-Pad2)") (class "Default")
      (node (ref "SW2") (pin "2") (pinfunction "2_2") (pintype "unspecified+no_connect"))
    )
    (net (code "59") (name "unconnected-(U4-CC1-PadA5)") (class "Default")
      (node (ref "U4") (pin "A5") (pinfunction "CC1_A5") (pintype "unspecified+no_connect"))
    )
    (net (code "60") (name "unconnected-(U4-CC2-PadB5)") (class "Default")
      (node (ref "U4") (pin "B5") (pinfunction "CC2_B5") (pintype "unspecified+no_connect"))
    )
    (net (code "61") (name "unconnected-(U4-PadA2)") (class "Default")
      (node (ref "U4") (pin "A2") (pinfunction "A2_A2") (pintype "unspecified+no_connect"))
    )
    (net (code "62") (name "unconnected-(U4-PadA10)") (class "Default")
      (node (ref "U4") (pin "A10") (pinfunction "A10_A10") (pintype "unspecified+no_connect"))
    )
    (net (code "63") (name "unconnected-(U4-PadB2)") (class "Default")
      (node (ref "U4") (pin "B2") (pinfunction "B2_B2") (pintype "unspecified+no_connect"))
    )
    (net (code "64") (name "unconnected-(U4-PadB10)") (class "Default")
      (node (ref "U4") (pin "B10") (pinfunction "B10_B10") (pintype "unspecified+no_connect"))
    )
    (net (code "65") (name "unconnected-(U4-SBU1-PadA8)") (class "Default")
      (node (ref "U4") (pin "A8") (pinfunction "SBU1_A8") (pintype "unspecified+no_connect"))
    )
    (net (code "66") (name "unconnected-(U4-SBU2-PadB8)") (class "Default")
      (node (ref "U4") (pin "B8") (pinfunction "SBU2_B8") (pintype "unspecified+no_connect"))
    )
    (net (code "67") (name "unconnected-(U4-VBUS-PadA4)") (class "Default")
      (node (ref "U4") (pin "A4") (pinfunction "VBUS_A4") (pintype "unspecified+no_connect"))
    )
    (net (code "68") (name "unconnected-(U4-VBUS-PadA9)") (class "Default")
      (node (ref "U4") (pin "A9") (pinfunction "VBUS_A9") (pintype "unspecified+no_connect"))
    )
    (net (code "69") (name "unconnected-(U4-VBUS-PadB4)") (class "Default")
      (node (ref "U4") (pin "B4") (pinfunction "VBUS_B4") (pintype "unspecified+no_connect"))
    )
    (net (code "70") (name "unconnected-(U4-VBUS-PadB9)") (class "Default")
      (node (ref "U4") (pin "B9") (pinfunction "VBUS_B9") (pintype "unspecified+no_connect"))
    )
    (net (code "71") (name "unconnected-(U5-RTS#-Pad4)") (class "Default")
      (node (ref "U5") (pin "4") (pinfunction "RTS#_4") (pintype "unspecified+no_connect"))
    )
    (net (code "72") (name "unconnected-(U6-RTS#-Pad4)") (class "Default")
      (node (ref "U6") (pin "4") (pinfunction "RTS#_4") (pintype "unspecified+no_connect"))
    )
    (net (code "73") (name "unconnected-(U7-PA4-Pad20)") (class "Default")
      (node (ref "U7") (pin "20") (pinfunction "PA4_20") (pintype "unspecified"))
    )
    (net (code "74") (name "unconnected-(U7-PA5-Pad21)") (class "Default")
      (node (ref "U7") (pin "21") (pinfunction "PA5_21") (pintype "unspecified"))
    )
    (net (code "75") (name "unconnected-(U7-PA12-Pad45)") (class "Default")
      (node (ref "U7") (pin "45") (pinfunction "PA12_45") (pintype "unspecified"))
    )
    (net (code "76") (name "unconnected-(U7-PA15-Pad50)") (class "Default")
      (node (ref "U7") (pin "50") (pinfunction "PA15_50") (pintype "unspecified"))
    )
    (net (code "77") (name "unconnected-(U7-PB2-Pad28)") (class "Default")
      (node (ref "U7") (pin "28") (pinfunction "PB2_28") (pintype "unspecified"))
    )
    (net (code "78") (name "unconnected-(U7-PB3-Pad55)") (class "Default")
      (node (ref "U7") (pin "55") (pinfunction "PB3_55") (pintype "unspecified"))
    )
    (net (code "79") (name "unconnected-(U7-PB5-Pad57)") (class "Default")
      (node (ref "U7") (pin "57") (pinfunction "PB5_57") (pintype "unspecified"))
    )
    (net (code "80") (name "unconnected-(U7-PB12-Pad33)") (class "Default")
      (node (ref "U7") (pin "33") (pinfunction "PB12_33") (pintype "unspecified"))
    )
    (net (code "81") (name "unconnected-(U7-PB13-Pad34)") (class "Default")
      (node (ref "U7") (pin "34") (pinfunction "PB13_34") (pintype "unspecified"))
    )
    (net (code "82") (name "unconnected-(U7-PC0-Pad8)") (class "Default")
      (node (ref "U7") (pin "8") (pinfunction "PC0_8") (pintype "unspecified"))
    )
    (net (code "83") (name "unconnected-(U7-PC3-Pad11)") (class "Default")
      (node (ref "U7") (pin "11") (pinfunction "PC3_11") (pintype "unspecified"))
    )
    (net (code "84") (name "unconnected-(U7-PC4-Pad24)") (class "Default")
      (node (ref "U7") (pin "24") (pinfunction "PC4_24") (pintype "unspecified"))
    )
    (net (code "85") (name "unconnected-(U7-PC5-Pad25)") (class "Default")
      (node (ref "U7") (pin "25") (pinfunction "PC5_25") (pintype "unspecified"))
    )
    (net (code "86") (name "unconnected-(U7-PC6-Pad37)") (class "Default")
      (node (ref "U7") (pin "37") (pinfunction "PC6_37") (pintype "unspecified"))
    )
    (net (code "87") (name "unconnected-(U7-PC9-Pad40)") (class "Default")
      (node (ref "U7") (pin "40") (pinfunction "PC9_40") (pintype "unspecified"))
    )
    (net (code "88") (name "unconnected-(U7-PC13-TAMPER-RTC-Pad2)") (class "Default")
      (node (ref "U7") (pin "2") (pinfunction "PC13-TAMPER-RTC_2") (pintype "unspecified"))
    )
    (net (code "89") (name "unconnected-(U7-PC14-OSC32_IN-Pad3)") (class "Default")
      (node (ref "U7") (pin "3") (pinfunction "PC14-OSC32_IN_3") (pintype "unspecified"))
    )
    (net (code "90") (name "unconnected-(U7-PC15-OSC32_OUT-Pad4)") (class "Default")
      (node (ref "U7") (pin "4") (pinfunction "PC15-OSC32_OUT_4") (pintype "unspecified"))
    )
    (net (code "91") (name "unconnected-(U8-1-PadDO2)") (class "Default")
      (node (ref "U8") (pin "DO2") (pinfunction "1_DO2") (pintype "input+no_connect"))
    )
    (net (code "92") (name "unconnected-(U8-6-PadDO1)") (class "Default")
      (node (ref "U8") (pin "DO1") (pinfunction "6_DO1") (pintype "input+no_connect"))
    )
    (net (code "93") (name "unconnected-(U8-7-PadD2)") (class "Default")
      (node (ref "U8") (pin "D2") (pinfunction "7_D2") (pintype "input+no_connect"))
    )
    (net (code "94") (name "unconnected-(U8-8-Pad5VCC)") (class "Default")
      (node (ref "U8") (pin "5VCC") (pinfunction "8_5VCC") (pintype "input+no_connect"))
    )
    (net (code "95") (name "unconnected-(U8-9-PadNC1)") (class "Default")
      (node (ref "U8") (pin "NC1") (pinfunction "9_NC1") (pintype "input+no_connect"))
    )
    (net (code "96") (name "unconnected-(U8-10-PadNC2)") (class "Default")
      (node (ref "U8") (pin "NC2") (pinfunction "10_NC2") (pintype "input+no_connect"))
    )
    (net (code "97") (name "unconnected-(U8-11-PadGND2)") (class "Default")
      (node (ref "U8") (pin "GND2") (pinfunction "11_GND2") (pintype "input+no_connect"))
    )
    (net (code "98") (name "unconnected-(U8-12-PadC3)") (class "Default")
      (node (ref "U8") (pin "C3") (pinfunction "12_C3") (pintype "input+no_connect"))
    )
    (net (code "99") (name "unconnected-(USB2-SBU1-Pad9)") (class "Default")
      (node (ref "USB2") (pin "9") (pinfunction "SBU1_9") (pintype "unspecified+no_connect"))
    )
    (net (code "100") (name "unconnected-(USB2-SBU2-Pad3)") (class "Default")
      (node (ref "USB2") (pin "3") (pinfunction "SBU2_3") (pintype "unspecified+no_connect"))
    )
  )
)
